# 08_eMMC.net
KiCad netlist of a schematic drawn in Altium Designer
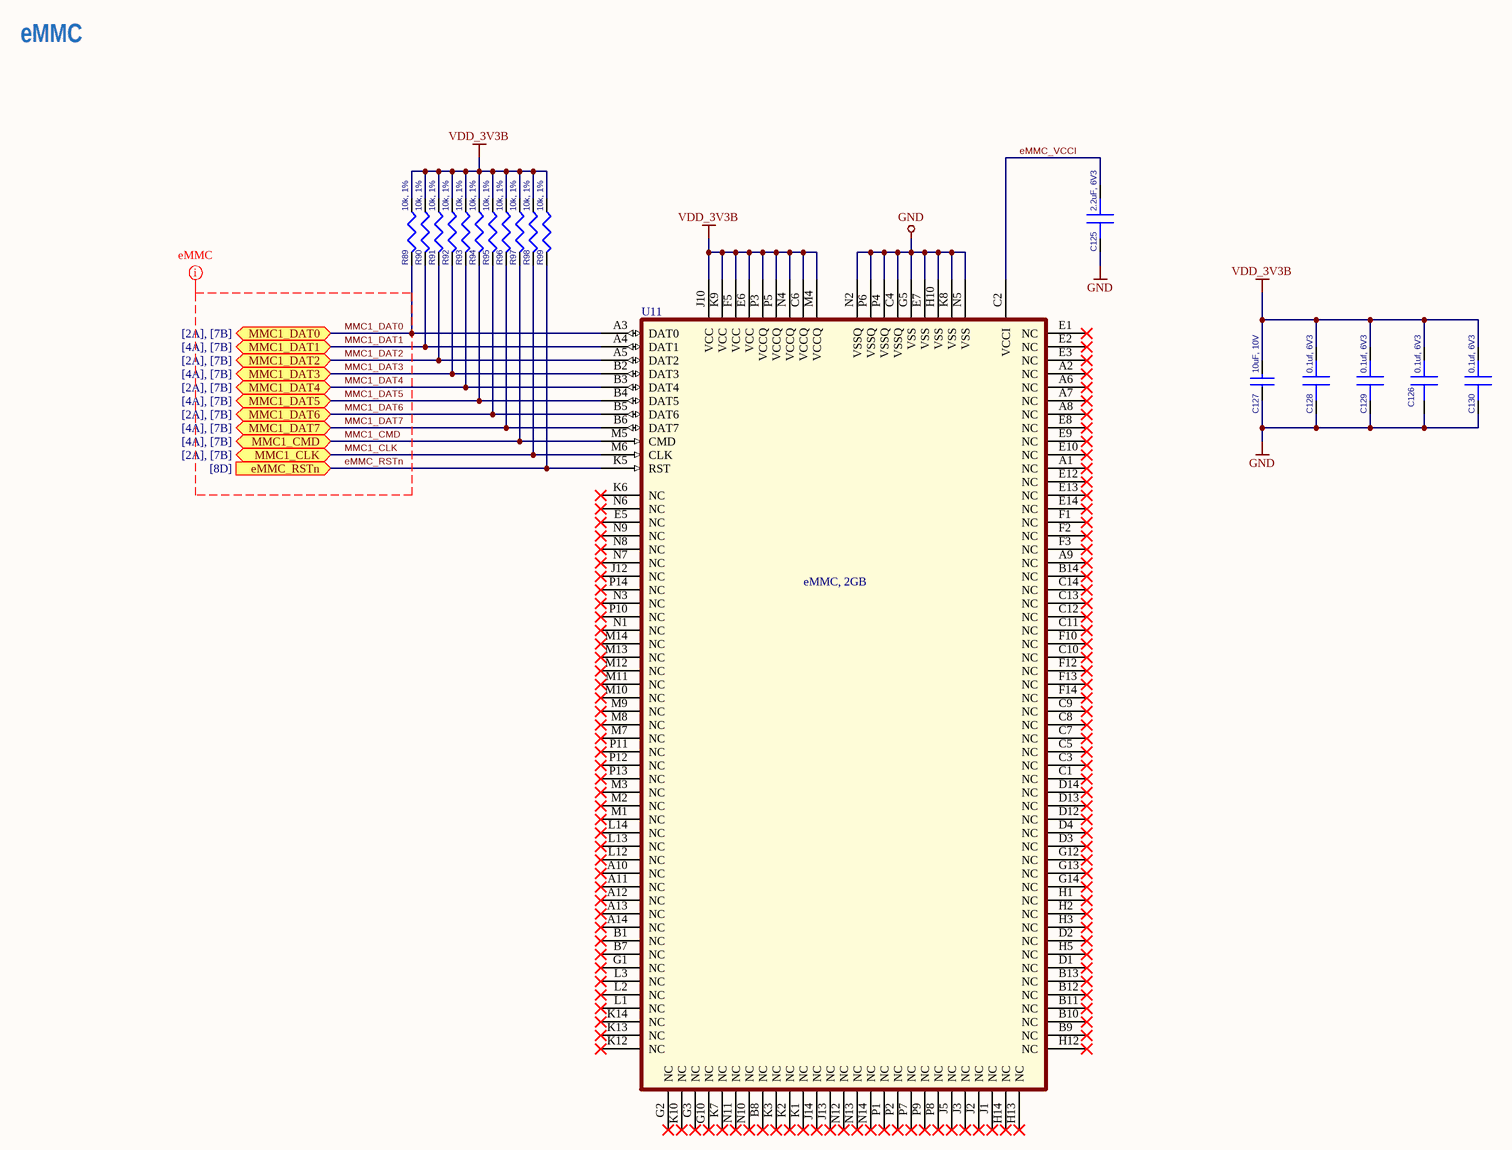
[diagram p0: 08_eMMC.SchDoc]

(export (version "E")
  (design (tool "Eeschema 10.0.6"))
  (components
    (comp (ref "C125")
      (value "2.2uF, 6V3")
      (footprint "402")
      (description "CAP CER 2.2UF 6.3V 10% X5R 0402")
      (fields
        (field (name "MANUFACTURER") "TDK Corporation")
        (field (name "MANUFACTURER PART NUMBER") "C1005X5R0J225K050BC")
      )
      (libsource (lib "BEAGLEBONEBLACK_REV A5B") (part "CAP SMD"))
    )
    (comp (ref "C126")
      (value "0.1uf, 6V3")
      (footprint "402")
      (description "CAP CER 0.1UF 6.3V 10% X5R 0402")
      (fields
        (field (name "MANUFACTURER") "TDK Corporation")
        (field (name "MANUFACTURER PART NUMBER") "C1005X5R0J104K050BA")
      )
      (libsource (lib "BEAGLEBONEBLACK_REV A5B") (part "CAP SMD"))
    )
    (comp (ref "C127")
      (value "10uF, 10V")
      (footprint "805")
      (description "CAP CER 10UF 10V Y5V 0805")
      (fields
        (field (name "MANUFACTURER") "TDK Corporation")
        (field (name "MANUFACTURER PART NUMBER") "C2012Y5V1A106Z")
      )
      (libsource (lib "BEAGLEBONEBLACK_REV A5B") (part "CAP_4.7uF_X5R_6.3V_10%_0603"))
    )
    (comp (ref "C128")
      (value "0.1uf, 6V3")
      (footprint "402")
      (description "CAP CER 0.1UF 6.3V 10% X5R 0402")
      (fields
        (field (name "MANUFACTURER") "TDK Corporation")
        (field (name "MANUFACTURER PART NUMBER") "C1005X5R0J104K050BA")
      )
      (libsource (lib "BEAGLEBONEBLACK_REV A5B") (part "CAP SMD"))
    )
    (comp (ref "C129")
      (value "0.1uf, 6V3")
      (footprint "402")
      (description "CAP CER 0.1UF 6.3V 10% X5R 0402")
      (fields
        (field (name "MANUFACTURER") "TDK Corporation")
        (field (name "MANUFACTURER PART NUMBER") "C1005X5R0J104K050BA")
      )
      (libsource (lib "BEAGLEBONEBLACK_REV A5B") (part "CAP SMD"))
    )
    (comp (ref "C130")
      (value "0.1uf, 6V3")
      (footprint "402")
      (description "CAP CER 0.1UF 6.3V 10% X5R 0402")
      (fields
        (field (name "MANUFACTURER") "TDK Corporation")
        (field (name "MANUFACTURER PART NUMBER") "C1005X5R0J104K050BA")
      )
      (libsource (lib "BEAGLEBONEBLACK_REV A5B") (part "CAP SMD"))
    )
    (comp (ref "R89")
      (value "10k, 1%")
      (footprint "402")
      (description "RES 10K OHM 1/16W 5% 0402 SMD")
      (fields
        (field (name "MANUFACTURER") "Rohm Semiconductor")
        (field (name "MANUFACTURER PART NUMBER") "MCR01MZPJ103")
      )
      (libsource (lib "BEAGLEBONEBLACK_REV A5B") (part "RES_10K_1/16W_1%_0402"))
    )
    (comp (ref "R90")
      (value "10k, 1%")
      (footprint "402")
      (description "RES 10K OHM 1/16W 5% 0402 SMD")
      (fields
        (field (name "MANUFACTURER") "Rohm Semiconductor")
        (field (name "MANUFACTURER PART NUMBER") "MCR01MZPJ103")
      )
      (libsource (lib "BEAGLEBONEBLACK_REV A5B") (part "RES_10K_1/16W_1%_0402"))
    )
    (comp (ref "R91")
      (value "10k, 1%")
      (footprint "402")
      (description "RES 10K OHM 1/16W 5% 0402 SMD")
      (fields
        (field (name "MANUFACTURER") "Rohm Semiconductor")
        (field (name "MANUFACTURER PART NUMBER") "MCR01MZPJ103")
      )
      (libsource (lib "BEAGLEBONEBLACK_REV A5B") (part "RES_10K_1/16W_1%_0402"))
    )
    (comp (ref "R92")
      (value "10k, 1%")
      (footprint "402")
      (description "RES 10K OHM 1/16W 5% 0402 SMD")
      (fields
        (field (name "MANUFACTURER") "Rohm Semiconductor")
        (field (name "MANUFACTURER PART NUMBER") "MCR01MZPJ103")
      )
      (libsource (lib "BEAGLEBONEBLACK_REV A5B") (part "RES_10K_1/16W_1%_0402"))
    )
    (comp (ref "R93")
      (value "10k, 1%")
      (footprint "402")
      (description "RES 10K OHM 1/16W 5% 0402 SMD")
      (fields
        (field (name "MANUFACTURER") "Rohm Semiconductor")
        (field (name "MANUFACTURER PART NUMBER") "MCR01MZPJ103")
      )
      (libsource (lib "BEAGLEBONEBLACK_REV A5B") (part "RES_10K_1/16W_1%_0402"))
    )
    (comp (ref "R94")
      (value "10k, 1%")
      (footprint "402")
      (description "RES 10K OHM 1/16W 5% 0402 SMD")
      (fields
        (field (name "MANUFACTURER") "Rohm Semiconductor")
        (field (name "MANUFACTURER PART NUMBER") "MCR01MZPJ103")
      )
      (libsource (lib "BEAGLEBONEBLACK_REV A5B") (part "RES_10K_1/16W_1%_0402"))
    )
    (comp (ref "R95")
      (value "10k, 1%")
      (footprint "402")
      (description "RES 10K OHM 1/16W 5% 0402 SMD")
      (fields
        (field (name "MANUFACTURER") "Rohm Semiconductor")
        (field (name "MANUFACTURER PART NUMBER") "MCR01MZPJ103")
      )
      (libsource (lib "BEAGLEBONEBLACK_REV A5B") (part "RES_10K_1/16W_1%_0402"))
    )
    (comp (ref "R96")
      (value "10k, 1%")
      (footprint "402")
      (description "RES 10K OHM 1/16W 5% 0402 SMD")
      (fields
        (field (name "MANUFACTURER") "Rohm Semiconductor")
        (field (name "MANUFACTURER PART NUMBER") "MCR01MZPJ103")
      )
      (libsource (lib "BEAGLEBONEBLACK_REV A5B") (part "RES_10K_1/16W_1%_0402"))
    )
    (comp (ref "R97")
      (value "10k, 1%")
      (footprint "402")
      (description "RES 10K OHM 1/16W 5% 0402 SMD")
      (fields
        (field (name "MANUFACTURER") "Rohm Semiconductor")
        (field (name "MANUFACTURER PART NUMBER") "MCR01MZPJ103")
      )
      (libsource (lib "BEAGLEBONEBLACK_REV A5B") (part "RES_10K_1/16W_1%_0402"))
    )
    (comp (ref "R98")
      (value "10k, 1%")
      (footprint "402")
      (description "RES 10K OHM 1/16W 5% 0402 SMD")
      (fields
        (field (name "MANUFACTURER") "Rohm Semiconductor")
        (field (name "MANUFACTURER PART NUMBER") "MCR01MZPJ103")
      )
      (libsource (lib "BEAGLEBONEBLACK_REV A5B") (part "RES_10K_1/16W_1%_0402"))
    )
    (comp (ref "R99")
      (value "10k, 1%")
      (footprint "402")
      (description "RES 10K OHM 1/16W 5% 0402 SMD")
      (fields
        (field (name "MANUFACTURER") "Rohm Semiconductor")
        (field (name "MANUFACTURER PART NUMBER") "MCR01MZPJ103")
      )
      (libsource (lib "BEAGLEBONEBLACK_REV A5B") (part "RES_10K_1/16W_1%_0402"))
    )
    (comp (ref "U11")
      (value "eMMC, 2GB")
      (footprint "BGA153_P14_P5_11P5X13")
      (description "Flash Card 2G-byte 3.3V MultiMedia Card 153-Pin WFBGA")
      (fields
        (field (name "MANUFACTURER") "Micron Technology")
        (field (name "MANUFACTURER PART NUMBER") "MTFC2GMVEA-0M WT")
      )
      (libsource (lib "BEAGLEBONEBLACK_REV A5B") (part "eMMC"))
    )
  )
  (nets
    (net (code "1") (name "/MMC1_CLK") (class "Default")
      (node (ref "R98") (pin "2") (pinfunction "2_2") (pintype "passive"))
      (node (ref "U11") (pin "M6") (pinfunction "CLK_M6") (pintype "input"))
    )
    (net (code "2") (name "/MMC1_CMD") (class "Default")
      (node (ref "R97") (pin "2") (pinfunction "2_2") (pintype "passive"))
      (node (ref "U11") (pin "M5") (pinfunction "CMD_M5") (pintype "input"))
    )
    (net (code "3") (name "/MMC1_DAT0") (class "Default")
      (node (ref "R89") (pin "2") (pinfunction "2_2") (pintype "passive"))
      (node (ref "U11") (pin "A3") (pinfunction "DAT0_A3") (pintype "bidirectional"))
    )
    (net (code "4") (name "/MMC1_DAT1") (class "Default")
      (node (ref "R90") (pin "2") (pinfunction "2_2") (pintype "passive"))
      (node (ref "U11") (pin "A4") (pinfunction "DAT1_A4") (pintype "bidirectional"))
    )
    (net (code "5") (name "/MMC1_DAT2") (class "Default")
      (node (ref "R91") (pin "2") (pinfunction "2_2") (pintype "passive"))
      (node (ref "U11") (pin "A5") (pinfunction "DAT2_A5") (pintype "bidirectional"))
    )
    (net (code "6") (name "/MMC1_DAT3") (class "Default")
      (node (ref "R92") (pin "2") (pinfunction "2_2") (pintype "passive"))
      (node (ref "U11") (pin "B2") (pinfunction "DAT3_B2") (pintype "bidirectional"))
    )
    (net (code "7") (name "/MMC1_DAT4") (class "Default")
      (node (ref "R93") (pin "2") (pinfunction "2_2") (pintype "passive"))
      (node (ref "U11") (pin "B3") (pinfunction "DAT4_B3") (pintype "bidirectional"))
    )
    (net (code "8") (name "/MMC1_DAT5") (class "Default")
      (node (ref "R94") (pin "2") (pinfunction "2_2") (pintype "passive"))
      (node (ref "U11") (pin "B4") (pinfunction "DAT5_B4") (pintype "bidirectional"))
    )
    (net (code "9") (name "/MMC1_DAT6") (class "Default")
      (node (ref "R95") (pin "2") (pinfunction "2_2") (pintype "passive"))
      (node (ref "U11") (pin "B5") (pinfunction "DAT6_B5") (pintype "bidirectional"))
    )
    (net (code "10") (name "/MMC1_DAT7") (class "Default")
      (node (ref "R96") (pin "2") (pinfunction "2_2") (pintype "passive"))
      (node (ref "U11") (pin "B6") (pinfunction "DAT7_B6") (pintype "bidirectional"))
    )
    (net (code "11") (name "/eMMC_RSTn") (class "Default")
      (node (ref "R99") (pin "2") (pinfunction "2_2") (pintype "passive"))
      (node (ref "U11") (pin "K5") (pinfunction "RST_K5") (pintype "input"))
    )
    (net (code "12") (name "/eMMC_VCCI") (class "Default")
      (node (ref "C125") (pin "1") (pinfunction "1_1") (pintype "passive"))
      (node (ref "U11") (pin "C2") (pinfunction "VCCI_C2") (pintype "power_in"))
    )
    (net (code "13") (name "GND") (class "Default")
      (node (ref "C125") (pin "2") (pinfunction "2_2") (pintype "passive"))
      (node (ref "C126") (pin "2") (pinfunction "2_2") (pintype "passive"))
      (node (ref "C127") (pin "1") (pinfunction "1_1") (pintype "passive"))
      (node (ref "C128") (pin "2") (pinfunction "2_2") (pintype "passive"))
      (node (ref "C129") (pin "2") (pinfunction "2_2") (pintype "passive"))
      (node (ref "C130") (pin "2") (pinfunction "2_2") (pintype "passive"))
      (node (ref "U11") (pin "C4") (pinfunction "VSSQ_C4") (pintype "power_in"))
      (node (ref "U11") (pin "E7") (pinfunction "VSS_E7") (pintype "power_in"))
      (node (ref "U11") (pin "G5") (pinfunction "VSS_G5") (pintype "power_in"))
      (node (ref "U11") (pin "H10") (pinfunction "VSS_H10") (pintype "power_in"))
      (node (ref "U11") (pin "K8") (pinfunction "VSS_K8") (pintype "power_in"))
      (node (ref "U11") (pin "N2") (pinfunction "VSSQ_N2") (pintype "power_in"))
      (node (ref "U11") (pin "N5") (pinfunction "VSS_N5") (pintype "power_in"))
      (node (ref "U11") (pin "P4") (pinfunction "VSSQ_P4") (pintype "power_in"))
      (node (ref "U11") (pin "P6") (pinfunction "VSSQ_P6") (pintype "power_in"))
    )
    (net (code "14") (name "VDD_3V3B") (class "Default")
      (node (ref "C126") (pin "1") (pinfunction "1_1") (pintype "passive"))
      (node (ref "C127") (pin "2") (pinfunction "2_2") (pintype "passive"))
      (node (ref "C128") (pin "1") (pinfunction "1_1") (pintype "passive"))
      (node (ref "C129") (pin "1") (pinfunction "1_1") (pintype "passive"))
      (node (ref "C130") (pin "1") (pinfunction "1_1") (pintype "passive"))
      (node (ref "R89") (pin "1") (pinfunction "1_1") (pintype "passive"))
      (node (ref "R90") (pin "1") (pinfunction "1_1") (pintype "passive"))
      (node (ref "R91") (pin "1") (pinfunction "1_1") (pintype "passive"))
      (node (ref "R92") (pin "1") (pinfunction "1_1") (pintype "passive"))
      (node (ref "R93") (pin "1") (pinfunction "1_1") (pintype "passive"))
      (node (ref "R94") (pin "1") (pinfunction "1_1") (pintype "passive"))
      (node (ref "R95") (pin "1") (pinfunction "1_1") (pintype "passive"))
      (node (ref "R96") (pin "1") (pinfunction "1_1") (pintype "passive"))
      (node (ref "R97") (pin "1") (pinfunction "1_1") (pintype "passive"))
      (node (ref "R98") (pin "1") (pinfunction "1_1") (pintype "passive"))
      (node (ref "R99") (pin "1") (pinfunction "1_1") (pintype "passive"))
      (node (ref "U11") (pin "C6") (pinfunction "VCCQ_C6") (pintype "power_in"))
      (node (ref "U11") (pin "E6") (pinfunction "VCC_E6") (pintype "power_in"))
      (node (ref "U11") (pin "F5") (pinfunction "VCC_F5") (pintype "power_in"))
      (node (ref "U11") (pin "J10") (pinfunction "VCC_J10") (pintype "power_in"))
      (node (ref "U11") (pin "K9") (pinfunction "VCC_K9") (pintype "power_in"))
      (node (ref "U11") (pin "M4") (pinfunction "VCCQ_M4") (pintype "power_in"))
      (node (ref "U11") (pin "N4") (pinfunction "VCCQ_N4") (pintype "power_in"))
      (node (ref "U11") (pin "P3") (pinfunction "VCCQ_P3") (pintype "power_in"))
      (node (ref "U11") (pin "P5") (pinfunction "VCCQ_P5") (pintype "power_in"))
    )
    (net (code "15") (name "unconnected-(U11-NC-PadA1)") (class "Default")
      (node (ref "U11") (pin "A1") (pinfunction "NC_A1") (pintype "passive+no_connect"))
    )
    (net (code "16") (name "unconnected-(U11-NC-PadA2)") (class "Default")
      (node (ref "U11") (pin "A2") (pinfunction "NC_A2") (pintype "passive+no_connect"))
    )
    (net (code "17") (name "unconnected-(U11-NC-PadA6)") (class "Default")
      (node (ref "U11") (pin "A6") (pinfunction "NC_A6") (pintype "passive+no_connect"))
    )
    (net (code "18") (name "unconnected-(U11-NC-PadA7)") (class "Default")
      (node (ref "U11") (pin "A7") (pinfunction "NC_A7") (pintype "passive+no_connect"))
    )
    (net (code "19") (name "unconnected-(U11-NC-PadA8)") (class "Default")
      (node (ref "U11") (pin "A8") (pinfunction "NC_A8") (pintype "passive+no_connect"))
    )
    (net (code "20") (name "unconnected-(U11-NC-PadA9)") (class "Default")
      (node (ref "U11") (pin "A9") (pinfunction "NC_A9") (pintype "passive+no_connect"))
    )
    (net (code "21") (name "unconnected-(U11-NC-PadA10)") (class "Default")
      (node (ref "U11") (pin "A10") (pinfunction "NC_A10") (pintype "passive+no_connect"))
    )
    (net (code "22") (name "unconnected-(U11-NC-PadA11)") (class "Default")
      (node (ref "U11") (pin "A11") (pinfunction "NC_A11") (pintype "passive+no_connect"))
    )
    (net (code "23") (name "unconnected-(U11-NC-PadA12)") (class "Default")
      (node (ref "U11") (pin "A12") (pinfunction "NC_A12") (pintype "passive+no_connect"))
    )
    (net (code "24") (name "unconnected-(U11-NC-PadA13)") (class "Default")
      (node (ref "U11") (pin "A13") (pinfunction "NC_A13") (pintype "passive+no_connect"))
    )
    (net (code "25") (name "unconnected-(U11-NC-PadA14)") (class "Default")
      (node (ref "U11") (pin "A14") (pinfunction "NC_A14") (pintype "passive+no_connect"))
    )
    (net (code "26") (name "unconnected-(U11-NC-PadB1)") (class "Default")
      (node (ref "U11") (pin "B1") (pinfunction "NC_B1") (pintype "passive+no_connect"))
    )
    (net (code "27") (name "unconnected-(U11-NC-PadB7)") (class "Default")
      (node (ref "U11") (pin "B7") (pinfunction "NC_B7") (pintype "passive+no_connect"))
    )
    (net (code "28") (name "unconnected-(U11-NC-PadB8)") (class "Default")
      (node (ref "U11") (pin "B8") (pinfunction "NC_B8") (pintype "passive+no_connect"))
    )
    (net (code "29") (name "unconnected-(U11-NC-PadB9)") (class "Default")
      (node (ref "U11") (pin "B9") (pinfunction "NC_B9") (pintype "passive+no_connect"))
    )
    (net (code "30") (name "unconnected-(U11-NC-PadB10)") (class "Default")
      (node (ref "U11") (pin "B10") (pinfunction "NC_B10") (pintype "passive+no_connect"))
    )
    (net (code "31") (name "unconnected-(U11-NC-PadB11)") (class "Default")
      (node (ref "U11") (pin "B11") (pinfunction "NC_B11") (pintype "passive+no_connect"))
    )
    (net (code "32") (name "unconnected-(U11-NC-PadB12)") (class "Default")
      (node (ref "U11") (pin "B12") (pinfunction "NC_B12") (pintype "passive+no_connect"))
    )
    (net (code "33") (name "unconnected-(U11-NC-PadB13)") (class "Default")
      (node (ref "U11") (pin "B13") (pinfunction "NC_B13") (pintype "passive+no_connect"))
    )
    (net (code "34") (name "unconnected-(U11-NC-PadB14)") (class "Default")
      (node (ref "U11") (pin "B14") (pinfunction "NC_B14") (pintype "passive+no_connect"))
    )
    (net (code "35") (name "unconnected-(U11-NC-PadC1)") (class "Default")
      (node (ref "U11") (pin "C1") (pinfunction "NC_C1") (pintype "passive+no_connect"))
    )
    (net (code "36") (name "unconnected-(U11-NC-PadC3)") (class "Default")
      (node (ref "U11") (pin "C3") (pinfunction "NC_C3") (pintype "passive+no_connect"))
    )
    (net (code "37") (name "unconnected-(U11-NC-PadC5)") (class "Default")
      (node (ref "U11") (pin "C5") (pinfunction "NC_C5") (pintype "passive+no_connect"))
    )
    (net (code "38") (name "unconnected-(U11-NC-PadC7)") (class "Default")
      (node (ref "U11") (pin "C7") (pinfunction "NC_C7") (pintype "passive+no_connect"))
    )
    (net (code "39") (name "unconnected-(U11-NC-PadC8)") (class "Default")
      (node (ref "U11") (pin "C8") (pinfunction "NC_C8") (pintype "passive+no_connect"))
    )
    (net (code "40") (name "unconnected-(U11-NC-PadC9)") (class "Default")
      (node (ref "U11") (pin "C9") (pinfunction "NC_C9") (pintype "passive+no_connect"))
    )
    (net (code "41") (name "unconnected-(U11-NC-PadC10)") (class "Default")
      (node (ref "U11") (pin "C10") (pinfunction "NC_C10") (pintype "passive+no_connect"))
    )
    (net (code "42") (name "unconnected-(U11-NC-PadC11)") (class "Default")
      (node (ref "U11") (pin "C11") (pinfunction "NC_C11") (pintype "passive+no_connect"))
    )
    (net (code "43") (name "unconnected-(U11-NC-PadC12)") (class "Default")
      (node (ref "U11") (pin "C12") (pinfunction "NC_C12") (pintype "passive+no_connect"))
    )
    (net (code "44") (name "unconnected-(U11-NC-PadC13)") (class "Default")
      (node (ref "U11") (pin "C13") (pinfunction "NC_C13") (pintype "passive+no_connect"))
    )
    (net (code "45") (name "unconnected-(U11-NC-PadC14)") (class "Default")
      (node (ref "U11") (pin "C14") (pinfunction "NC_C14") (pintype "passive+no_connect"))
    )
    (net (code "46") (name "unconnected-(U11-NC-PadD1)") (class "Default")
      (node (ref "U11") (pin "D1") (pinfunction "NC_D1") (pintype "passive+no_connect"))
    )
    (net (code "47") (name "unconnected-(U11-NC-PadD2)") (class "Default")
      (node (ref "U11") (pin "D2") (pinfunction "NC_D2") (pintype "passive+no_connect"))
    )
    (net (code "48") (name "unconnected-(U11-NC-PadD3)") (class "Default")
      (node (ref "U11") (pin "D3") (pinfunction "NC_D3") (pintype "passive+no_connect"))
    )
    (net (code "49") (name "unconnected-(U11-NC-PadD4)") (class "Default")
      (node (ref "U11") (pin "D4") (pinfunction "NC_D4") (pintype "passive+no_connect"))
    )
    (net (code "50") (name "unconnected-(U11-NC-PadD12)") (class "Default")
      (node (ref "U11") (pin "D12") (pinfunction "NC_D12") (pintype "passive+no_connect"))
    )
    (net (code "51") (name "unconnected-(U11-NC-PadD13)") (class "Default")
      (node (ref "U11") (pin "D13") (pinfunction "NC_D13") (pintype "passive+no_connect"))
    )
    (net (code "52") (name "unconnected-(U11-NC-PadD14)") (class "Default")
      (node (ref "U11") (pin "D14") (pinfunction "NC_D14") (pintype "passive+no_connect"))
    )
    (net (code "53") (name "unconnected-(U11-NC-PadE1)") (class "Default")
      (node (ref "U11") (pin "E1") (pinfunction "NC_E1") (pintype "passive+no_connect"))
    )
    (net (code "54") (name "unconnected-(U11-NC-PadE2)") (class "Default")
      (node (ref "U11") (pin "E2") (pinfunction "NC_E2") (pintype "passive+no_connect"))
    )
    (net (code "55") (name "unconnected-(U11-NC-PadE3)") (class "Default")
      (node (ref "U11") (pin "E3") (pinfunction "NC_E3") (pintype "passive+no_connect"))
    )
    (net (code "56") (name "unconnected-(U11-NC-PadE5)") (class "Default")
      (node (ref "U11") (pin "E5") (pinfunction "NC_E5") (pintype "passive+no_connect"))
    )
    (net (code "57") (name "unconnected-(U11-NC-PadE8)") (class "Default")
      (node (ref "U11") (pin "E8") (pinfunction "NC_E8") (pintype "passive+no_connect"))
    )
    (net (code "58") (name "unconnected-(U11-NC-PadE9)") (class "Default")
      (node (ref "U11") (pin "E9") (pinfunction "NC_E9") (pintype "passive+no_connect"))
    )
    (net (code "59") (name "unconnected-(U11-NC-PadE10)") (class "Default")
      (node (ref "U11") (pin "E10") (pinfunction "NC_E10") (pintype "passive+no_connect"))
    )
    (net (code "60") (name "unconnected-(U11-NC-PadE12)") (class "Default")
      (node (ref "U11") (pin "E12") (pinfunction "NC_E12") (pintype "passive+no_connect"))
    )
    (net (code "61") (name "unconnected-(U11-NC-PadE13)") (class "Default")
      (node (ref "U11") (pin "E13") (pinfunction "NC_E13") (pintype "passive+no_connect"))
    )
    (net (code "62") (name "unconnected-(U11-NC-PadE14)") (class "Default")
      (node (ref "U11") (pin "E14") (pinfunction "NC_E14") (pintype "passive+no_connect"))
    )
    (net (code "63") (name "unconnected-(U11-NC-PadF1)") (class "Default")
      (node (ref "U11") (pin "F1") (pinfunction "NC_F1") (pintype "passive+no_connect"))
    )
    (net (code "64") (name "unconnected-(U11-NC-PadF2)") (class "Default")
      (node (ref "U11") (pin "F2") (pinfunction "NC_F2") (pintype "passive+no_connect"))
    )
    (net (code "65") (name "unconnected-(U11-NC-PadF3)") (class "Default")
      (node (ref "U11") (pin "F3") (pinfunction "NC_F3") (pintype "passive+no_connect"))
    )
    (net (code "66") (name "unconnected-(U11-NC-PadF10)") (class "Default")
      (node (ref "U11") (pin "F10") (pinfunction "NC_F10") (pintype "passive+no_connect"))
    )
    (net (code "67") (name "unconnected-(U11-NC-PadF12)") (class "Default")
      (node (ref "U11") (pin "F12") (pinfunction "NC_F12") (pintype "passive+no_connect"))
    )
    (net (code "68") (name "unconnected-(U11-NC-PadF13)") (class "Default")
      (node (ref "U11") (pin "F13") (pinfunction "NC_F13") (pintype "passive+no_connect"))
    )
    (net (code "69") (name "unconnected-(U11-NC-PadF14)") (class "Default")
      (node (ref "U11") (pin "F14") (pinfunction "NC_F14") (pintype "passive+no_connect"))
    )
    (net (code "70") (name "unconnected-(U11-NC-PadG1)") (class "Default")
      (node (ref "U11") (pin "G1") (pinfunction "NC_G1") (pintype "passive+no_connect"))
    )
    (net (code "71") (name "unconnected-(U11-NC-PadG2)") (class "Default")
      (node (ref "U11") (pin "G2") (pinfunction "NC_G2") (pintype "passive+no_connect"))
    )
    (net (code "72") (name "unconnected-(U11-NC-PadG3)") (class "Default")
      (node (ref "U11") (pin "G3") (pinfunction "NC_G3") (pintype "passive+no_connect"))
    )
    (net (code "73") (name "unconnected-(U11-NC-PadG10)") (class "Default")
      (node (ref "U11") (pin "G10") (pinfunction "NC_G10") (pintype "passive+no_connect"))
    )
    (net (code "74") (name "unconnected-(U11-NC-PadG12)") (class "Default")
      (node (ref "U11") (pin "G12") (pinfunction "NC_G12") (pintype "passive+no_connect"))
    )
    (net (code "75") (name "unconnected-(U11-NC-PadG13)") (class "Default")
      (node (ref "U11") (pin "G13") (pinfunction "NC_G13") (pintype "passive+no_connect"))
    )
    (net (code "76") (name "unconnected-(U11-NC-PadG14)") (class "Default")
      (node (ref "U11") (pin "G14") (pinfunction "NC_G14") (pintype "passive+no_connect"))
    )
    (net (code "77") (name "unconnected-(U11-NC-PadH1)") (class "Default")
      (node (ref "U11") (pin "H1") (pinfunction "NC_H1") (pintype "passive+no_connect"))
    )
    (net (code "78") (name "unconnected-(U11-NC-PadH2)") (class "Default")
      (node (ref "U11") (pin "H2") (pinfunction "NC_H2") (pintype "passive+no_connect"))
    )
    (net (code "79") (name "unconnected-(U11-NC-PadH3)") (class "Default")
      (node (ref "U11") (pin "H3") (pinfunction "NC_H3") (pintype "passive+no_connect"))
    )
    (net (code "80") (name "unconnected-(U11-NC-PadH5)") (class "Default")
      (node (ref "U11") (pin "H5") (pinfunction "NC_H5") (pintype "passive+no_connect"))
    )
    (net (code "81") (name "unconnected-(U11-NC-PadH12)") (class "Default")
      (node (ref "U11") (pin "H12") (pinfunction "NC_H12") (pintype "passive+no_connect"))
    )
    (net (code "82") (name "unconnected-(U11-NC-PadH13)") (class "Default")
      (node (ref "U11") (pin "H13") (pinfunction "NC_H13") (pintype "passive+no_connect"))
    )
    (net (code "83") (name "unconnected-(U11-NC-PadH14)") (class "Default")
      (node (ref "U11") (pin "H14") (pinfunction "NC_H14") (pintype "passive+no_connect"))
    )
    (net (code "84") (name "unconnected-(U11-NC-PadJ1)") (class "Default")
      (node (ref "U11") (pin "J1") (pinfunction "NC_J1") (pintype "passive+no_connect"))
    )
    (net (code "85") (name "unconnected-(U11-NC-PadJ2)") (class "Default")
      (node (ref "U11") (pin "J2") (pinfunction "NC_J2") (pintype "passive+no_connect"))
    )
    (net (code "86") (name "unconnected-(U11-NC-PadJ3)") (class "Default")
      (node (ref "U11") (pin "J3") (pinfunction "NC_J3") (pintype "passive+no_connect"))
    )
    (net (code "87") (name "unconnected-(U11-NC-PadJ5)") (class "Default")
      (node (ref "U11") (pin "J5") (pinfunction "NC_J5") (pintype "passive+no_connect"))
    )
    (net (code "88") (name "unconnected-(U11-NC-PadJ12)") (class "Default")
      (node (ref "U11") (pin "J12") (pinfunction "NC_J12") (pintype "passive+no_connect"))
    )
    (net (code "89") (name "unconnected-(U11-NC-PadJ13)") (class "Default")
      (node (ref "U11") (pin "J13") (pinfunction "NC_J13") (pintype "passive+no_connect"))
    )
    (net (code "90") (name "unconnected-(U11-NC-PadJ14)") (class "Default")
      (node (ref "U11") (pin "J14") (pinfunction "NC_J14") (pintype "passive+no_connect"))
    )
    (net (code "91") (name "unconnected-(U11-NC-PadK1)") (class "Default")
      (node (ref "U11") (pin "K1") (pinfunction "NC_K1") (pintype "passive+no_connect"))
    )
    (net (code "92") (name "unconnected-(U11-NC-PadK2)") (class "Default")
      (node (ref "U11") (pin "K2") (pinfunction "NC_K2") (pintype "passive+no_connect"))
    )
    (net (code "93") (name "unconnected-(U11-NC-PadK3)") (class "Default")
      (node (ref "U11") (pin "K3") (pinfunction "NC_K3") (pintype "passive+no_connect"))
    )
    (net (code "94") (name "unconnected-(U11-NC-PadK6)") (class "Default")
      (node (ref "U11") (pin "K6") (pinfunction "NC_K6") (pintype "passive+no_connect"))
    )
    (net (code "95") (name "unconnected-(U11-NC-PadK7)") (class "Default")
      (node (ref "U11") (pin "K7") (pinfunction "NC_K7") (pintype "passive+no_connect"))
    )
    (net (code "96") (name "unconnected-(U11-NC-PadK10)") (class "Default")
      (node (ref "U11") (pin "K10") (pinfunction "NC_K10") (pintype "passive+no_connect"))
    )
    (net (code "97") (name "unconnected-(U11-NC-PadK12)") (class "Default")
      (node (ref "U11") (pin "K12") (pinfunction "NC_K12") (pintype "passive+no_connect"))
    )
    (net (code "98") (name "unconnected-(U11-NC-PadK13)") (class "Default")
      (node (ref "U11") (pin "K13") (pinfunction "NC_K13") (pintype "passive+no_connect"))
    )
    (net (code "99") (name "unconnected-(U11-NC-PadK14)") (class "Default")
      (node (ref "U11") (pin "K14") (pinfunction "NC_K14") (pintype "passive+no_connect"))
    )
    (net (code "100") (name "unconnected-(U11-NC-PadL1)") (class "Default")
      (node (ref "U11") (pin "L1") (pinfunction "NC_L1") (pintype "passive+no_connect"))
    )
    (net (code "101") (name "unconnected-(U11-NC-PadL2)") (class "Default")
      (node (ref "U11") (pin "L2") (pinfunction "NC_L2") (pintype "passive+no_connect"))
    )
    (net (code "102") (name "unconnected-(U11-NC-PadL3)") (class "Default")
      (node (ref "U11") (pin "L3") (pinfunction "NC_L3") (pintype "passive+no_connect"))
    )
    (net (code "103") (name "unconnected-(U11-NC-PadL12)") (class "Default")
      (node (ref "U11") (pin "L12") (pinfunction "NC_L12") (pintype "passive+no_connect"))
    )
    (net (code "104") (name "unconnected-(U11-NC-PadL13)") (class "Default")
      (node (ref "U11") (pin "L13") (pinfunction "NC_L13") (pintype "passive+no_connect"))
    )
    (net (code "105") (name "unconnected-(U11-NC-PadL14)") (class "Default")
      (node (ref "U11") (pin "L14") (pinfunction "NC_L14") (pintype "passive+no_connect"))
    )
    (net (code "106") (name "unconnected-(U11-NC-PadM1)") (class "Default")
      (node (ref "U11") (pin "M1") (pinfunction "NC_M1") (pintype "passive+no_connect"))
    )
    (net (code "107") (name "unconnected-(U11-NC-PadM2)") (class "Default")
      (node (ref "U11") (pin "M2") (pinfunction "NC_M2") (pintype "passive+no_connect"))
    )
    (net (code "108") (name "unconnected-(U11-NC-PadM3)") (class "Default")
      (node (ref "U11") (pin "M3") (pinfunction "NC_M3") (pintype "passive+no_connect"))
    )
    (net (code "109") (name "unconnected-(U11-NC-PadM7)") (class "Default")
      (node (ref "U11") (pin "M7") (pinfunction "NC_M7") (pintype "passive+no_connect"))
    )
    (net (code "110") (name "unconnected-(U11-NC-PadM8)") (class "Default")
      (node (ref "U11") (pin "M8") (pinfunction "NC_M8") (pintype "passive+no_connect"))
    )
    (net (code "111") (name "unconnected-(U11-NC-PadM9)") (class "Default")
      (node (ref "U11") (pin "M9") (pinfunction "NC_M9") (pintype "passive+no_connect"))
    )
    (net (code "112") (name "unconnected-(U11-NC-PadM10)") (class "Default")
      (node (ref "U11") (pin "M10") (pinfunction "NC_M10") (pintype "passive+no_connect"))
    )
    (net (code "113") (name "unconnected-(U11-NC-PadM11)") (class "Default")
      (node (ref "U11") (pin "M11") (pinfunction "NC_M11") (pintype "passive+no_connect"))
    )
    (net (code "114") (name "unconnected-(U11-NC-PadM12)") (class "Default")
      (node (ref "U11") (pin "M12") (pinfunction "NC_M12") (pintype "passive+no_connect"))
    )
    (net (code "115") (name "unconnected-(U11-NC-PadM13)") (class "Default")
      (node (ref "U11") (pin "M13") (pinfunction "NC_M13") (pintype "passive+no_connect"))
    )
    (net (code "116") (name "unconnected-(U11-NC-PadM14)") (class "Default")
      (node (ref "U11") (pin "M14") (pinfunction "NC_M14") (pintype "passive+no_connect"))
    )
    (net (code "117") (name "unconnected-(U11-NC-PadN1)") (class "Default")
      (node (ref "U11") (pin "N1") (pinfunction "NC_N1") (pintype "passive+no_connect"))
    )
    (net (code "118") (name "unconnected-(U11-NC-PadN3)") (class "Default")
      (node (ref "U11") (pin "N3") (pinfunction "NC_N3") (pintype "passive+no_connect"))
    )
    (net (code "119") (name "unconnected-(U11-NC-PadN6)") (class "Default")
      (node (ref "U11") (pin "N6") (pinfunction "NC_N6") (pintype "passive+no_connect"))
    )
    (net (code "120") (name "unconnected-(U11-NC-PadN7)") (class "Default")
      (node (ref "U11") (pin "N7") (pinfunction "NC_N7") (pintype "passive+no_connect"))
    )
    (net (code "121") (name "unconnected-(U11-NC-PadN8)") (class "Default")
      (node (ref "U11") (pin "N8") (pinfunction "NC_N8") (pintype "passive+no_connect"))
    )
    (net (code "122") (name "unconnected-(U11-NC-PadN9)") (class "Default")
      (node (ref "U11") (pin "N9") (pinfunction "NC_N9") (pintype "passive+no_connect"))
    )
    (net (code "123") (name "unconnected-(U11-NC-PadN10)") (class "Default")
      (node (ref "U11") (pin "N10") (pinfunction "NC_N10") (pintype "passive+no_connect"))
    )
    (net (code "124") (name "unconnected-(U11-NC-PadN11)") (class "Default")
      (node (ref "U11") (pin "N11") (pinfunction "NC_N11") (pintype "passive+no_connect"))
    )
    (net (code "125") (name "unconnected-(U11-NC-PadN12)") (class "Default")
      (node (ref "U11") (pin "N12") (pinfunction "NC_N12") (pintype "passive+no_connect"))
    )
    (net (code "126") (name "unconnected-(U11-NC-PadN13)") (class "Default")
      (node (ref "U11") (pin "N13") (pinfunction "NC_N13") (pintype "passive+no_connect"))
    )
    (net (code "127") (name "unconnected-(U11-NC-PadN14)") (class "Default")
      (node (ref "U11") (pin "N14") (pinfunction "NC_N14") (pintype "passive+no_connect"))
    )
    (net (code "128") (name "unconnected-(U11-NC-PadP1)") (class "Default")
      (node (ref "U11") (pin "P1") (pinfunction "NC_P1") (pintype "passive+no_connect"))
    )
    (net (code "129") (name "unconnected-(U11-NC-PadP2)") (class "Default")
      (node (ref "U11") (pin "P2") (pinfunction "NC_P2") (pintype "passive+no_connect"))
    )
    (net (code "130") (name "unconnected-(U11-NC-PadP7)") (class "Default")
      (node (ref "U11") (pin "P7") (pinfunction "NC_P7") (pintype "passive+no_connect"))
    )
    (net (code "131") (name "unconnected-(U11-NC-PadP8)") (class "Default")
      (node (ref "U11") (pin "P8") (pinfunction "NC_P8") (pintype "passive+no_connect"))
    )
    (net (code "132") (name "unconnected-(U11-NC-PadP9)") (class "Default")
      (node (ref "U11") (pin "P9") (pinfunction "NC_P9") (pintype "passive+no_connect"))
    )
    (net (code "133") (name "unconnected-(U11-NC-PadP10)") (class "Default")
      (node (ref "U11") (pin "P10") (pinfunction "NC_P10") (pintype "passive+no_connect"))
    )
    (net (code "134") (name "unconnected-(U11-NC-PadP11)") (class "Default")
      (node (ref "U11") (pin "P11") (pinfunction "NC_P11") (pintype "passive+no_connect"))
    )
    (net (code "135") (name "unconnected-(U11-NC-PadP12)") (class "Default")
      (node (ref "U11") (pin "P12") (pinfunction "NC_P12") (pintype "passive+no_connect"))
    )
    (net (code "136") (name "unconnected-(U11-NC-PadP13)") (class "Default")
      (node (ref "U11") (pin "P13") (pinfunction "NC_P13") (pintype "passive+no_connect"))
    )
    (net (code "137") (name "unconnected-(U11-NC-PadP14)") (class "Default")
      (node (ref "U11") (pin "P14") (pinfunction "NC_P14") (pintype "passive+no_connect"))
    )
  )
)
